# MiniHeating2.net
KiCad netlist of a schematic drawn in Altium Designer
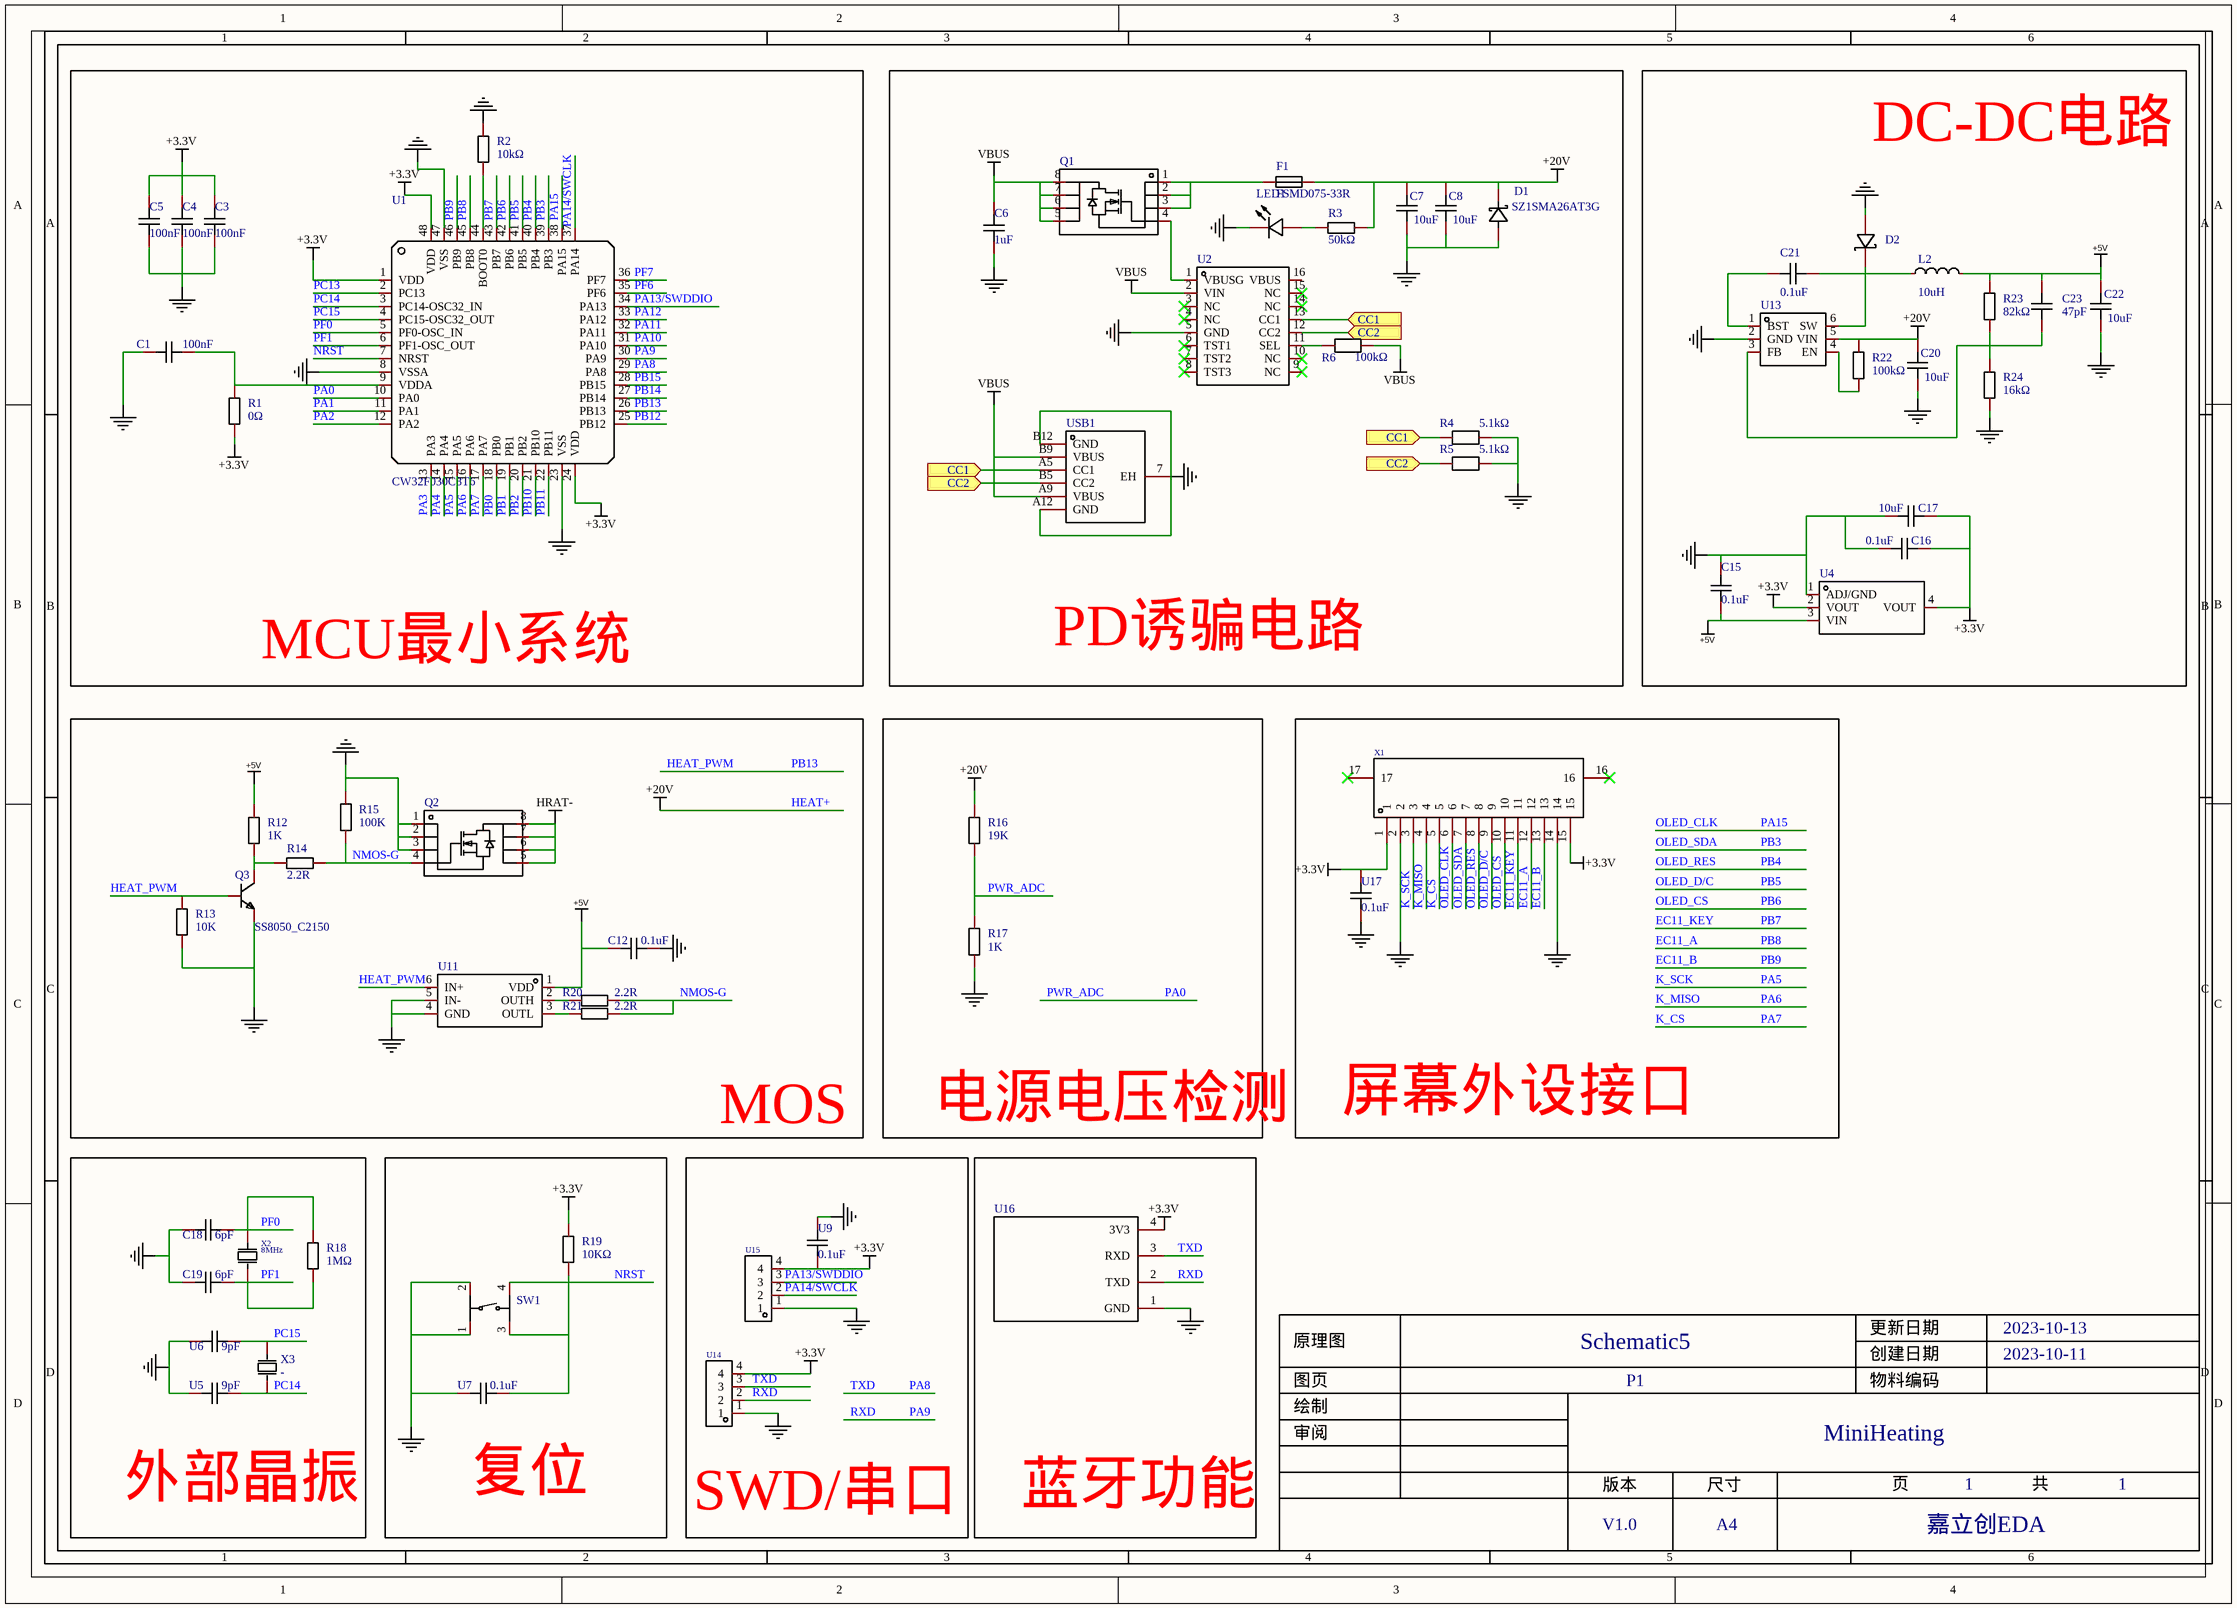
[diagram p0: MiniHeating2.schdoc]

(export (version "E")
  (design (tool "Eeschema 10.0.6"))
  (components
    (comp (ref "C1")
      (value "100nF")
      (description "容值:100nF;精度:±10%;额定电压:50V;材质(温度系数):X7R;")
      (fields
        (field (name "MANUFACTURER") "YAGEO(国巨)")
        (field (name "MANUFACTURER PART") "CC0603KRX7R9BB104")
      )
      (libsource (lib "altium-import") (part "root_0_CC0603KRX7R9BB104_"))
    )
    (comp (ref "C3")
      (value "100nF")
      (description "容值:100nF;精度:±10%;额定电压:50V;材质(温度系数):X7R;")
      (fields
        (field (name "MANUFACTURER") "YAGEO(国巨)")
        (field (name "MANUFACTURER PART") "CC0603KRX7R9BB104")
      )
      (libsource (lib "altium-import") (part "root_1_CC0603KRX7R9BB104_"))
    )
    (comp (ref "C4")
      (value "100nF")
      (description "容值:100nF;精度:±10%;额定电压:50V;材质(温度系数):X7R;")
      (fields
        (field (name "MANUFACTURER") "YAGEO(国巨)")
        (field (name "MANUFACTURER PART") "CC0603KRX7R9BB104")
      )
      (libsource (lib "altium-import") (part "root_1_CC0603KRX7R9BB104_"))
    )
    (comp (ref "C5")
      (value "100nF")
      (description "容值:100nF;精度:±10%;额定电压:50V;材质(温度系数):X7R;")
      (fields
        (field (name "MANUFACTURER") "YAGEO(国巨)")
        (field (name "MANUFACTURER PART") "CC0603KRX7R9BB104")
      )
      (libsource (lib "altium-import") (part "root_1_CC0603KRX7R9BB104_"))
    )
    (comp (ref "C6")
      (value "1uF")
      (description "容值:10uF;精度:±20%;额定电压:16V;材质(温度系数):-;")
      (fields (field (name "MANUFACTURER") "SAMSUNG(三星)") (field (name "MANUFACTURER PART") "10uF"))
      (libsource (lib "altium-import") (part "root_0_10uF_C15415_"))
    )
    (comp (ref "C7")
      (value "10uF")
      (description "容值:10uF;精度:±10%;额定电压:-;材质(温度系数):-;")
      (fields
        (field (name "NAME") "10uF")
        (field (name "MANUFACTURER") "muRata(村田)")
        (field (name "MANUFACTURER PART") "GRT21BC71E106KE13L")
      )
      (libsource (lib "altium-import") (part "root_1_GRT21BC71E106KE13L_"))
    )
    (comp (ref "C8")
      (value "10uF")
      (description "容值:10uF;精度:±10%;额定电压:-;材质(温度系数):-;")
      (fields
        (field (name "NAME") "10uF")
        (field (name "MANUFACTURER") "muRata(村田)")
        (field (name "MANUFACTURER PART") "GRT21BC71E106KE13L")
      )
      (libsource (lib "altium-import") (part "root_1_GRT21BC71E106KE13L_"))
    )
    (comp (ref "C12")
      (value "0.1uF")
      (description "容值:9pF;额定电压:50V;材质(温度系数):C0G;")
      (fields (field (name "MANUFACTURER") "TDK") (field (name "MANUFACTURER PART") "C1608C0G1H090D080AA"))
      (libsource (lib "altium-import") (part "root_0_C1608C0G1H090D080AA_"))
    )
    (comp (ref "C15")
      (value "0.1uF")
      (description "容值:0.1uF;精度:±10%;额定电压:50V;温度系数:-;")
      (fields
        (field (name "MANUFACTURER") "Knowles(楼氏)")
        (field (name "MANUFACTURER PART") "0603BB104K500NGT")
      )
      (libsource (lib "altium-import") (part "root_1_0603BB104K500NGT_"))
    )
    (comp (ref "C16")
      (value "0.1uF")
      (description "容值:0.1uF;精度:±10%;额定电压:50V;温度系数:-;")
      (fields
        (field (name "MANUFACTURER") "Knowles(楼氏)")
        (field (name "MANUFACTURER PART") "0603BB104K500NGT")
      )
      (libsource (lib "altium-import") (part "root_2_0603BB104K500NGT_"))
    )
    (comp (ref "C17")
      (value "10uF")
      (description "容值:10uF;精度:±10%;额定电压:-;材质(温度系数):-;")
      (fields
        (field (name "NAME") "10uF")
        (field (name "MANUFACTURER") "muRata(村田)")
        (field (name "MANUFACTURER PART") "GRT21BC71E106KE13L")
      )
      (libsource (lib "altium-import") (part "root_2_GRT21BC71E106KE13L_"))
    )
    (comp (ref "C18")
      (value "6pF")
      (description "容值:6pF;额定电压:50V;材质(温度系数):C0G;")
      (fields (field (name "MANUFACTURER") "TDK") (field (name "MANUFACTURER PART") "CGA3E2C0G1H060DT0Y0N"))
      (libsource (lib "altium-import") (part "root_0_CGA3E2C0G1H060DT0Y0N_"))
    )
    (comp (ref "C19")
      (value "6pF")
      (description "容值:6pF;额定电压:50V;材质(温度系数):C0G;")
      (fields (field (name "MANUFACTURER") "TDK") (field (name "MANUFACTURER PART") "CGA3E2C0G1H060DT0Y0N"))
      (libsource (lib "altium-import") (part "root_0_CGA3E2C0G1H060DT0Y0N_"))
    )
    (comp (ref "C20")
      (value "10uF")
      (description "容值:10uF;精度:±10%;额定电压:-;材质(温度系数):-;")
      (fields
        (field (name "NAME") "10uF")
        (field (name "MANUFACTURER") "muRata(村田)")
        (field (name "MANUFACTURER PART") "GRT21BC71E106KE13L")
      )
      (libsource (lib "altium-import") (part "root_1_GRT21BC71E106KE13L_"))
    )
    (comp (ref "C21")
      (value "0.1uF")
      (description "容值:0.1uF;精度:±10%;额定电压:50V;温度系数:-;")
      (fields
        (field (name "MANUFACTURER") "Knowles(楼氏)")
        (field (name "MANUFACTURER PART") "0603BB104K500NGT")
      )
      (libsource (lib "altium-import") (part "root_0_0603BB104K500NGT_"))
    )
    (comp (ref "C22")
      (value "10uF")
      (description "容值:10uF;精度:±10%;额定电压:-;材质(温度系数):-;")
      (fields
        (field (name "NAME") "10uF")
        (field (name "MANUFACTURER") "muRata(村田)")
        (field (name "MANUFACTURER PART") "GRT21BC71E106KE13L")
      )
      (libsource (lib "altium-import") (part "root_1_GRT21BC71E106KE13L_"))
    )
    (comp (ref "C23")
      (value "47pF")
      (description "容值:0.1uF;精度:±10%;额定电压:50V;温度系数:-;")
      (fields
        (field (name "MANUFACTURER") "Knowles(楼氏)")
        (field (name "MANUFACTURER PART") "0603BB104K500NGT")
      )
      (libsource (lib "altium-import") (part "root_1_0603BB104K500NGT_"))
    )
    (comp (ref "D1")
      (value "SZ1SMA26AT3G")
      (fields (field (name "NAME") "SZ1SMA26AT3G") (field (name "MANUFACTURER") "Littelfuse(美国力特)"))
      (libsource (lib "altium-import") (part "root_3_SZ1SMA26AT3G_"))
    )
    (comp (ref "D2")
      (value "SS34_C8678")
      (description "二极管配置:独立式;直流反向耐压(Vr):40V;平均整流电流(Io):3A;正向压降(Vf):550mV@3A;")
      (fields (field (name "MANUFACTURER") "MDD") (field (name "MANUFACTURER PART") "SS34"))
      (libsource (lib "altium-import") (part "root_1_SS34_C8678_"))
    )
    (comp (ref "F1")
      (value "FSMD075-33R")
      (description "最大电压:33V;最大电流:40A;保持电流:750mA;跳闸电流:1.5A;")
      (fields (field (name "NAME") "FSMD075-33R") (field (name "MANUFACTURER") "FUZETEC(台湾富致)"))
      (libsource (lib "altium-import") (part "root_0_FSMD075-33R_"))
    )
    (comp (ref "L2")
      (value "10uH")
      (description "类型:-;电感值:10uH;精度:±20%;额定电流:2.45A;饱和电流(Isat):3.5A;")
      (fields (field (name "MANUFACTURER") "Sunlord(顺络)") (field (name "MANUFACTURER PART") "SWPA6045S100MT"))
      (libsource (lib "altium-import") (part "root_0_SWPA6045S100MT_"))
    )
    (comp (ref "LED1")
      (value "KT-0603R")
      (description "发光颜色:红灯;二极管配置:-;透镜颜色:-;主波长:-;色温:-;功率:-;发光角度:-;安装方式:-;工作温度:-40℃~+85℃;")
      (fields (field (name "MANUFACTURER") "KENTO"))
      (libsource (lib "altium-import") (part "root_0_KT-0603R_"))
    )
    (comp (ref "Q1")
      (value "BSC123N08NS3 G")
      (libsource (lib "altium-import") (part "root_0_mirrored_BSC123N08NS3 G_"))
    )
    (comp (ref "Q2")
      (value "BSC123N08NS3 G")
      (libsource (lib "altium-import") (part "root_0_BSC123N08NS3 G_"))
    )
    (comp (ref "Q3")
      (value "SS8050_C2150")
      (description "晶体管类型:NPN;集射极击穿电压(Vceo):25V;集电极电流(Ic):1.5A;功率(Pd):300mW;直流电流增益(hFE@Ic,Vce):200@100mA,1V;")
      (fields
        (field (name "DEVICE") "SS8050_C2150")
        (field (name "MANUFACTURER") "CJ(江苏长电/长晶)")
        (field (name "MANUFACTURER PART") "SS8050")
      )
      (libsource (lib "altium-import") (part "root_0_SS8050_C2150_"))
    )
    (comp (ref "R1")
      (value "0Ω")
      (description "电阻类型:厚膜电阻;阻值:470kΩ;精度:±1%;功率:100mW;")
      (fields
        (field (name "MANUFACTURER") "UNI-ROYAL(厚声)")
        (field (name "MANUFACTURER PART") "0603WAF4703T5E")
      )
      (libsource (lib "altium-import") (part "root_1_0603WAF4703T5E_"))
    )
    (comp (ref "R2")
      (value "10kΩ")
      (description "电阻类型:厚膜电阻;阻值:24kΩ;精度:±1%;功率:100mW;")
      (fields
        (field (name "MANUFACTURER") "UNI-ROYAL(厚声)")
        (field (name "MANUFACTURER PART") "0603WAF2402T5E")
      )
      (libsource (lib "altium-import") (part "root_1_0603WAF2402T5E_"))
    )
    (comp (ref "R3")
      (value "50kΩ")
      (description "电阻类型:薄膜电阻;阻值:10kΩ;精度:±0.1%;功率:63mW;")
      (fields
        (field (name "MANUFACTURER") "SEI(Stackpole Electronics Inc.)")
        (field (name "MANUFACTURER PART") "RNCS0603BKE10K0")
      )
      (libsource (lib "altium-import") (part "root_2_RNCS0603BKE10K0_"))
    )
    (comp (ref "R4")
      (value "5.1kΩ")
      (description "电阻类型:厚膜电阻;阻值:10kΩ;精度:±0.5%;功率:100mW;")
      (fields (field (name "MANUFACTURER") "YAGEO(国巨)") (field (name "MANUFACTURER PART") "AC0603DR-0710KL"))
      (libsource (lib "altium-import") (part "root_0_AC0603DR-0710KL_"))
    )
    (comp (ref "R5")
      (value "5.1kΩ")
      (description "电阻类型:厚膜电阻;阻值:10kΩ;精度:±0.5%;功率:100mW;")
      (fields (field (name "MANUFACTURER") "YAGEO(国巨)") (field (name "MANUFACTURER PART") "AC0603DR-0710KL"))
      (libsource (lib "altium-import") (part "root_0_AC0603DR-0710KL_"))
    )
    (comp (ref "R6")
      (value "100kΩ")
      (description "阻值:100kΩ;功率:125mW;")
      (fields
        (field (name "NAME") "100kΩ")
        (field (name "MANUFACTURER") "Milliohm(毫欧)")
        (field (name "MANUFACTURER PART") "HoLTT0805-1/8W-100K-5%")
      )
      (libsource (lib "altium-import") (part "root_0_HoLTT0805-1/8W-100K-5%_"))
    )
    (comp (ref "R12")
      (value "1K")
      (description "电阻类型:厚膜电阻;阻值:470kΩ;精度:±1%;功率:100mW;")
      (fields
        (field (name "MANUFACTURER") "UNI-ROYAL(厚声)")
        (field (name "MANUFACTURER PART") "0603WAF4703T5E")
      )
      (libsource (lib "altium-import") (part "root_1_0603WAF4703T5E_"))
    )
    (comp (ref "R13")
      (value "10K")
      (description "电阻类型:厚膜电阻;阻值:470kΩ;精度:±1%;功率:100mW;")
      (fields
        (field (name "MANUFACTURER") "UNI-ROYAL(厚声)")
        (field (name "MANUFACTURER PART") "0603WAF4703T5E")
      )
      (libsource (lib "altium-import") (part "root_1_0603WAF4703T5E_"))
    )
    (comp (ref "R14")
      (value "2.2R")
      (description "电阻类型:厚膜电阻;阻值:470kΩ;精度:±1%;功率:100mW;")
      (fields
        (field (name "MANUFACTURER") "UNI-ROYAL(厚声)")
        (field (name "MANUFACTURER PART") "0603WAF4703T5E")
      )
      (libsource (lib "altium-import") (part "root_2_0603WAF4703T5E_"))
    )
    (comp (ref "R15")
      (value "100K")
      (description "电阻类型:厚膜电阻;阻值:470kΩ;精度:±1%;功率:100mW;")
      (fields
        (field (name "MANUFACTURER") "UNI-ROYAL(厚声)")
        (field (name "MANUFACTURER PART") "0603WAF4703T5E")
      )
      (libsource (lib "altium-import") (part "root_1_0603WAF4703T5E_"))
    )
    (comp (ref "R16")
      (value "19K")
      (description "电阻类型:厚膜电阻;阻值:470kΩ;精度:±1%;功率:100mW;")
      (fields
        (field (name "MANUFACTURER") "UNI-ROYAL(厚声)")
        (field (name "MANUFACTURER PART") "0603WAF4703T5E")
      )
      (libsource (lib "altium-import") (part "root_1_0603WAF4703T5E_"))
    )
    (comp (ref "R17")
      (value "1K")
      (description "电阻类型:厚膜电阻;阻值:470kΩ;精度:±1%;功率:100mW;")
      (fields
        (field (name "MANUFACTURER") "UNI-ROYAL(厚声)")
        (field (name "MANUFACTURER PART") "0603WAF4703T5E")
      )
      (libsource (lib "altium-import") (part "root_1_0603WAF4703T5E_"))
    )
    (comp (ref "R18")
      (value "1MΩ")
      (description "电阻类型:厚膜电阻;阻值:1MΩ;精度:±1%;功率:100mW;")
      (fields
        (field (name "MANUFACTURER") "UNI-ROYAL(厚声)")
        (field (name "MANUFACTURER PART") "0603WAF1004T5E")
      )
      (libsource (lib "altium-import") (part "root_1_0603WAF1004T5E_"))
    )
    (comp (ref "R19")
      (value "10KΩ")
      (description "电阻类型:厚膜电阻;阻值:1MΩ;精度:±1%;功率:100mW;")
      (fields
        (field (name "MANUFACTURER") "UNI-ROYAL(厚声)")
        (field (name "MANUFACTURER PART") "0603WAF1004T5E")
      )
      (libsource (lib "altium-import") (part "root_1_0603WAF1004T5E_"))
    )
    (comp (ref "R20")
      (value "2.2R")
      (description "电阻类型:厚膜电阻;阻值:470kΩ;精度:±1%;功率:100mW;")
      (fields
        (field (name "MANUFACTURER") "UNI-ROYAL(厚声)")
        (field (name "MANUFACTURER PART") "0603WAF4703T5E")
      )
      (libsource (lib "altium-import") (part "root_2_0603WAF4703T5E_"))
    )
    (comp (ref "R21")
      (value "2.2R")
      (description "电阻类型:厚膜电阻;阻值:470kΩ;精度:±1%;功率:100mW;")
      (fields
        (field (name "MANUFACTURER") "UNI-ROYAL(厚声)")
        (field (name "MANUFACTURER PART") "0603WAF4703T5E")
      )
      (libsource (lib "altium-import") (part "root_2_0603WAF4703T5E_"))
    )
    (comp (ref "R22")
      (value "100kΩ")
      (description "阻值:50kΩ;精度:±0.1%;功率:62.5mW;")
      (fields (field (name "MANUFACTURER") "Viking(光颉)") (field (name "MANUFACTURER PART") "AR03BTC5002A"))
      (libsource (lib "altium-import") (part "root_1_AR03BTC5002A_"))
    )
    (comp (ref "R23")
      (value "82kΩ")
      (description "阻值:50kΩ;精度:±0.1%;功率:62.5mW;")
      (fields (field (name "MANUFACTURER") "Viking(光颉)") (field (name "MANUFACTURER PART") "AR03BTC5002A"))
      (libsource (lib "altium-import") (part "root_1_AR03BTC5002A_"))
    )
    (comp (ref "R24")
      (value "16kΩ")
      (description "阻值:50kΩ;精度:±0.1%;功率:62.5mW;")
      (fields (field (name "MANUFACTURER") "Viking(光颉)") (field (name "MANUFACTURER PART") "AR03BTC5002A"))
      (libsource (lib "altium-import") (part "root_1_AR03BTC5002A_"))
    )
    (comp (ref "SW1")
      (value "TS-1186D-C-A")
      (description "触点电流:50mA;额定电压(DC):12V;绝缘电阻:-;电路结构:单刀单掷;安装方式:卧贴;带灯:无;作用力:260gf;机械寿命:10万次;带支架:否;")
      (fields (field (name "MANUFACTURER") "XKB Connectivity(中国星坤)"))
      (libsource (lib "altium-import") (part "root_1_TS-1186D-C-A_"))
    )
    (comp (ref "U1")
      (value "CW32F030C8T6")
      (fields (field (name "NAME") "CW32F030C8T6") (field (name "MANUFACTURER") "CW(芯源)"))
      (libsource (lib "altium-import") (part "root_0_CW32F030C8T6_C3019113_"))
    )
    (comp (ref "U2")
      (value "IP2721")
      (fields (field (name "MANUFACTURER") "INJOINIC(英集芯)"))
      (libsource (lib "altium-import") (part "root_0_IP2721_"))
    )
    (comp (ref "U4")
      (value "LM1117GS-3.3")
      (description "输出类型:-;")
      (fields (field (name "MANUFACTURER") "HTC"))
      (libsource (lib "altium-import") (part "root_0_LM1117GS-3.3_"))
    )
    (comp (ref "U5")
      (value "9pF")
      (description "容值:9pF;额定电压:50V;材质(温度系数):C0G;")
      (fields (field (name "MANUFACTURER") "TDK") (field (name "MANUFACTURER PART") "C1608C0G1H090D080AA"))
      (libsource (lib "altium-import") (part "root_0_C1608C0G1H090D080AA_"))
    )
    (comp (ref "U6")
      (value "9pF")
      (description "容值:9pF;额定电压:50V;材质(温度系数):C0G;")
      (fields (field (name "MANUFACTURER") "TDK") (field (name "MANUFACTURER PART") "C1608C0G1H090D080AA"))
      (libsource (lib "altium-import") (part "root_0_C1608C0G1H090D080AA_"))
    )
    (comp (ref "U7")
      (value "0.1uF")
      (description "容值:9pF;额定电压:50V;材质(温度系数):C0G;")
      (fields (field (name "MANUFACTURER") "TDK") (field (name "MANUFACTURER PART") "C1608C0G1H090D080AA"))
      (libsource (lib "altium-import") (part "root_0_C1608C0G1H090D080AA_"))
    )
    (comp (ref "U9")
      (value "0.1uF")
      (description "容值:9pF;额定电压:50V;材质(温度系数):C0G;")
      (fields (field (name "MANUFACTURER") "TDK") (field (name "MANUFACTURER PART") "C1608C0G1H090D080AA"))
      (libsource (lib "altium-import") (part "root_1_C1608C0G1H090D080AA_"))
    )
    (comp (ref "U11")
      (value "UCC27511DBVR")
      (description "驱动配置:低边;负载类型:MOSFET；IGBT;电源电压:4.5V~18V;峰值灌电流:8A;峰值拉电流:4A;")
      (fields (field (name "MANUFACTURER") "TI(德州仪器)"))
      (libsource (lib "altium-import") (part "root_0_mirrored_UCC27511DBVR_"))
    )
    (comp (ref "U13")
      (value "LGS5145")
      (description "功能类型:降压型;输出类型:可调;输入电压:4.5V~55V;输出电压:800mV~40V;输出电流(最大值):1A;")
      (fields (field (name "MANUFACTURER") "Legend-Si(棱晶半导体)"))
      (libsource (lib "altium-import") (part "root_0_LGS5145_"))
    )
    (comp (ref "U14")
      (value "ZX-PZ2.54-1-4PZZ")
      (fields (field (name "MANUFACTURER") "Megastar(兆星)"))
      (libsource (lib "altium-import") (part "root_2_ZX-PZ2.54-1-4PZZ_"))
    )
    (comp (ref "U15")
      (value "ZX-PZ2.54-1-4PZZ")
      (fields (field (name "MANUFACTURER") "Megastar(兆星)"))
      (libsource (lib "altium-import") (part "root_2_ZX-PZ2.54-1-4PZZ_"))
    )
    (comp (ref "U16")
      (value "ECB01H2")
      (description "ECB01H2模块")
      (libsource (lib "altium-import") (part "root_1_ECB01H2_"))
    )
    (comp (ref "U17")
      (value "0.1uF")
      (description "容值:9pF;额定电压:50V;材质(温度系数):C0G;")
      (fields (field (name "MANUFACTURER") "TDK") (field (name "MANUFACTURER PART") "C1608C0G1H090D080AA"))
      (libsource (lib "altium-import") (part "root_1_C1608C0G1H090D080AA_"))
    )
    (comp (ref "USB1")
      (value "TYPE-C-6P-DIP2X2")
      (libsource (lib "altium-import") (part "root_0_TYPE-C-6P-DIP2X2_"))
    )
    (comp (ref "X1")
      (value "AFC01-S15FCA-00")
      (description "间距:0.5mm;触点数量:15;锁定特性:翻盖式;安装类型:卧贴;触点类型:下接;工作温度范围:-;")
      (fields (field (name "MANUFACTURER") "JS(钜硕电子)"))
      (libsource (lib "altium-import") (part "root_1_AFC01-S15FCA-00_"))
    )
    (comp (ref "X2")
      (value "8MHz")
      (description "频率:8MHz;频率公差:±30ppm;负载电容:20pF;")
      (fields (field (name "MANUFACTURER") "TAE(雅晶鑫)") (field (name "MANUFACTURER PART") "TAXD8M2GLFBET2T"))
      (libsource (lib "altium-import") (part "root_1_TAXD8M2GLFBET2T_"))
    )
    (comp (ref "X3")
      (value "-")
      (description "频率:-;负载电容:-;")
      (fields (field (name "MANUFACTURER") "TKD(泰晶)") (field (name "MANUFACTURER PART") "SF32WK32768D31T002"))
      (libsource (lib "altium-import") (part "root_1_SF32WK32768D31T002_"))
    )
  )
  (nets
    (net (code "1") (name "+3.3V") (class "Default")
      (node (ref "C16") (pin "1") (pinfunction "1_1") (pintype "passive"))
      (node (ref "C17") (pin "1") (pinfunction "1_1") (pintype "passive"))
      (node (ref "C3") (pin "2") (pinfunction "2_2") (pintype "passive"))
      (node (ref "C4") (pin "2") (pinfunction "2_2") (pintype "passive"))
      (node (ref "C5") (pin "2") (pinfunction "2_2") (pintype "passive"))
      (node (ref "R1") (pin "1") (pinfunction "1_1") (pintype "passive"))
      (node (ref "R19") (pin "2") (pinfunction "2_2") (pintype "passive"))
      (node (ref "U1") (pin "1") (pinfunction "VDD_1") (pintype "passive"))
      (node (ref "U1") (pin "24") (pinfunction "VDD_24") (pintype "passive"))
      (node (ref "U1") (pin "48") (pinfunction "VDD_48") (pintype "passive"))
      (node (ref "U14") (pin "4") (pinfunction "4_4") (pintype "passive"))
      (node (ref "U15") (pin "4") (pinfunction "4_4") (pintype "passive"))
      (node (ref "U16") (pin "4") (pinfunction "3V3_4") (pintype "passive"))
      (node (ref "U17") (pin "2") (pinfunction "2_2") (pintype "passive"))
      (node (ref "U4") (pin "2") (pinfunction "VOUT_2") (pintype "passive"))
      (node (ref "U4") (pin "4") (pinfunction "VOUT_4") (pintype "passive"))
      (node (ref "U9") (pin "1") (pinfunction "1_1") (pintype "passive"))
      (node (ref "X1") (pin "1") (pinfunction "1_1") (pintype "passive"))
      (node (ref "X1") (pin "15") (pinfunction "15_15") (pintype "passive"))
    )
    (net (code "2") (name "+5V") (class "Default")
      (node (ref "C12") (pin "1") (pinfunction "1_1") (pintype "passive"))
      (node (ref "C15") (pin "1") (pinfunction "1_1") (pintype "passive"))
      (node (ref "C22") (pin "2") (pinfunction "2_2") (pintype "passive"))
      (node (ref "C23") (pin "2") (pinfunction "2_2") (pintype "passive"))
      (node (ref "L2") (pin "2") (pinfunction "2_2") (pintype "passive"))
      (node (ref "R12") (pin "2") (pinfunction "2_2") (pintype "passive"))
      (node (ref "R23") (pin "2") (pinfunction "2_2") (pintype "passive"))
      (node (ref "U11") (pin "1") (pinfunction "VDD_1") (pintype "passive"))
      (node (ref "U4") (pin "3") (pinfunction "VIN_3") (pintype "passive"))
    )
    (net (code "3") (name "+20V") (class "Default")
      (node (ref "C20") (pin "2") (pinfunction "2_2") (pintype "passive"))
      (node (ref "C7") (pin "2") (pinfunction "2_2") (pintype "passive"))
      (node (ref "C8") (pin "2") (pinfunction "2_2") (pintype "passive"))
      (node (ref "D1") (pin "2") (pinfunction "K_2") (pintype "passive"))
      (node (ref "F1") (pin "2") (pinfunction "2_2") (pintype "passive"))
      (node (ref "R16") (pin "2") (pinfunction "2_2") (pintype "passive"))
      (node (ref "R22") (pin "2") (pinfunction "2_2") (pintype "passive"))
      (node (ref "R3") (pin "1") (pinfunction "1_1") (pintype "passive"))
      (node (ref "U13") (pin "5") (pinfunction "VIN_5") (pintype "passive"))
    )
    (net (code "4") (name "/CC1") (class "Default")
      (node (ref "R4") (pin "1") (pinfunction "1_1") (pintype "passive"))
      (node (ref "U2") (pin "13") (pinfunction "CC1_13") (pintype "passive"))
      (node (ref "USB1") (pin "A5") (pinfunction "CC1_A5") (pintype "passive"))
    )
    (net (code "5") (name "/CC2") (class "Default")
      (node (ref "R5") (pin "1") (pinfunction "1_1") (pintype "passive"))
      (node (ref "U2") (pin "12") (pinfunction "CC2_12") (pintype "passive"))
      (node (ref "USB1") (pin "B5") (pinfunction "CC2_B5") (pintype "passive"))
    )
    (net (code "6") (name "/EC11_A") (class "Default")
      (node (ref "U1") (pin "45") (pinfunction "PB8_45") (pintype "passive"))
      (node (ref "X1") (pin "12") (pinfunction "12_12") (pintype "passive"))
    )
    (net (code "7") (name "/EC11_B") (class "Default")
      (node (ref "U1") (pin "46") (pinfunction "PB9_46") (pintype "passive"))
      (node (ref "X1") (pin "13") (pinfunction "13_13") (pintype "passive"))
    )
    (net (code "8") (name "/EC11_KEY") (class "Default")
      (node (ref "U1") (pin "43") (pinfunction "PB7_43") (pintype "passive"))
      (node (ref "X1") (pin "11") (pinfunction "11_11") (pintype "passive"))
    )
    (net (code "9") (name "/HEAT_PWM") (class "Default")
      (node (ref "Q3") (pin "1") (pinfunction "B_1") (pintype "passive"))
      (node (ref "R13") (pin "2") (pinfunction "2_2") (pintype "passive"))
      (node (ref "U1") (pin "26") (pinfunction "PB13_26") (pintype "passive"))
      (node (ref "U11") (pin "6") (pinfunction "IN+_6") (pintype "passive"))
    )
    (net (code "10") (name "/K_CS") (class "Default")
      (node (ref "U1") (pin "17") (pinfunction "PA7_17") (pintype "passive"))
      (node (ref "X1") (pin "5") (pinfunction "5_5") (pintype "passive"))
    )
    (net (code "11") (name "/K_MISO") (class "Default")
      (node (ref "U1") (pin "16") (pinfunction "PA6_16") (pintype "passive"))
      (node (ref "X1") (pin "4") (pinfunction "4_4") (pintype "passive"))
    )
    (net (code "12") (name "/K_SCK") (class "Default")
      (node (ref "U1") (pin "15") (pinfunction "PA5_15") (pintype "passive"))
      (node (ref "X1") (pin "3") (pinfunction "3_3") (pintype "passive"))
    )
    (net (code "13") (name "/NMOS-G") (class "Default")
      (node (ref "Q2") (pin "4") (pinfunction "G_4") (pintype "passive"))
      (node (ref "R14") (pin "1") (pinfunction "1_1") (pintype "passive"))
      (node (ref "R15") (pin "1") (pinfunction "1_1") (pintype "passive"))
      (node (ref "R20") (pin "1") (pinfunction "1_1") (pintype "passive"))
      (node (ref "R21") (pin "1") (pinfunction "1_1") (pintype "passive"))
    )
    (net (code "14") (name "/NRST") (class "Default")
      (node (ref "R19") (pin "1") (pinfunction "1_1") (pintype "passive"))
      (node (ref "SW1") (pin "3") (pinfunction "3_3") (pintype "passive"))
      (node (ref "SW1") (pin "4") (pinfunction "4_4") (pintype "passive"))
      (node (ref "U1") (pin "7") (pinfunction "NRST_7") (pintype "passive"))
      (node (ref "U7") (pin "2") (pinfunction "2_2") (pintype "passive"))
    )
    (net (code "15") (name "/OLED_CLK") (class "Default")
      (node (ref "U1") (pin "38") (pinfunction "PA15_38") (pintype "passive"))
      (node (ref "X1") (pin "6") (pinfunction "6_6") (pintype "passive"))
    )
    (net (code "16") (name "/OLED_CS") (class "Default")
      (node (ref "U1") (pin "42") (pinfunction "PB6_42") (pintype "passive"))
      (node (ref "X1") (pin "10") (pinfunction "10_10") (pintype "passive"))
    )
    (net (code "17") (name "/OLED_D{slash}C") (class "Default")
      (node (ref "U1") (pin "41") (pinfunction "PB5_41") (pintype "passive"))
      (node (ref "X1") (pin "9") (pinfunction "9_9") (pintype "passive"))
    )
    (net (code "18") (name "/OLED_RES") (class "Default")
      (node (ref "U1") (pin "40") (pinfunction "PB4_40") (pintype "passive"))
      (node (ref "X1") (pin "8") (pinfunction "8_8") (pintype "passive"))
    )
    (net (code "19") (name "/OLED_SDA") (class "Default")
      (node (ref "U1") (pin "39") (pinfunction "PB3_39") (pintype "passive"))
      (node (ref "X1") (pin "7") (pinfunction "7_7") (pintype "passive"))
    )
    (net (code "20") (name "/PA0") (class "Default")
      (node (ref "R16") (pin "1") (pinfunction "1_1") (pintype "passive"))
      (node (ref "R17") (pin "2") (pinfunction "2_2") (pintype "passive"))
      (node (ref "U1") (pin "10") (pinfunction "PA0_10") (pintype "passive"))
    )
    (net (code "21") (name "/PA1") (class "Default")
      (node (ref "U1") (pin "11") (pinfunction "PA1_11") (pintype "passive"))
    )
    (net (code "22") (name "/PA2") (class "Default")
      (node (ref "U1") (pin "12") (pinfunction "PA2_12") (pintype "passive"))
    )
    (net (code "23") (name "/PA3") (class "Default")
      (node (ref "U1") (pin "13") (pinfunction "PA3_13") (pintype "passive"))
    )
    (net (code "24") (name "/PA4") (class "Default")
      (node (ref "U1") (pin "14") (pinfunction "PA4_14") (pintype "passive"))
    )
    (net (code "25") (name "/PA8") (class "Default")
      (node (ref "U1") (pin "29") (pinfunction "PA8_29") (pintype "passive"))
      (node (ref "U14") (pin "3") (pinfunction "3_3") (pintype "passive"))
      (node (ref "U16") (pin "3") (pinfunction "RXD_3") (pintype "passive"))
    )
    (net (code "26") (name "/PA9") (class "Default")
      (node (ref "U1") (pin "30") (pinfunction "PA9_30") (pintype "passive"))
      (node (ref "U14") (pin "2") (pinfunction "2_2") (pintype "passive"))
      (node (ref "U16") (pin "2") (pinfunction "TXD_2") (pintype "passive"))
    )
    (net (code "27") (name "/PA10") (class "Default")
      (node (ref "U1") (pin "31") (pinfunction "PA10_31") (pintype "passive"))
    )
    (net (code "28") (name "/PA11") (class "Default")
      (node (ref "U1") (pin "32") (pinfunction "PA11_32") (pintype "passive"))
    )
    (net (code "29") (name "/PA12") (class "Default")
      (node (ref "U1") (pin "33") (pinfunction "PA12_33") (pintype "passive"))
    )
    (net (code "30") (name "/PA13{slash}SWDDIO") (class "Default")
      (node (ref "U1") (pin "34") (pinfunction "PA13_34") (pintype "passive"))
      (node (ref "U15") (pin "3") (pinfunction "3_3") (pintype "passive"))
    )
    (net (code "31") (name "/PA14{slash}SWCLK") (class "Default")
      (node (ref "U1") (pin "37") (pinfunction "PA14_37") (pintype "passive"))
      (node (ref "U15") (pin "2") (pinfunction "2_2") (pintype "passive"))
    )
    (net (code "32") (name "/PB0") (class "Default")
      (node (ref "U1") (pin "18") (pinfunction "PB0_18") (pintype "passive"))
    )
    (net (code "33") (name "/PB1") (class "Default")
      (node (ref "U1") (pin "19") (pinfunction "PB1_19") (pintype "passive"))
    )
    (net (code "34") (name "/PB2") (class "Default")
      (node (ref "U1") (pin "20") (pinfunction "PB2_20") (pintype "passive"))
    )
    (net (code "35") (name "/PB10") (class "Default")
      (node (ref "U1") (pin "21") (pinfunction "PB10_21") (pintype "passive"))
    )
    (net (code "36") (name "/PB11") (class "Default")
      (node (ref "U1") (pin "22") (pinfunction "PB11_22") (pintype "passive"))
    )
    (net (code "37") (name "/PB12") (class "Default")
      (node (ref "U1") (pin "25") (pinfunction "PB12_25") (pintype "passive"))
    )
    (net (code "38") (name "/PB14") (class "Default")
      (node (ref "U1") (pin "27") (pinfunction "PB14_27") (pintype "passive"))
    )
    (net (code "39") (name "/PB15") (class "Default")
      (node (ref "U1") (pin "28") (pinfunction "PB15_28") (pintype "passive"))
    )
    (net (code "40") (name "/PC13") (class "Default")
      (node (ref "U1") (pin "2") (pinfunction "PC13_2") (pintype "passive"))
    )
    (net (code "41") (name "/PC14") (class "Default")
      (node (ref "U1") (pin "3") (pinfunction "PC14-OSC32_IN_3") (pintype "passive"))
      (node (ref "U5") (pin "2") (pinfunction "2_2") (pintype "passive"))
      (node (ref "X3") (pin "1") (pinfunction "OSC1_1") (pintype "passive"))
    )
    (net (code "42") (name "/PC15") (class "Default")
      (node (ref "U1") (pin "4") (pinfunction "PC15-OSC32_OUT_4") (pintype "passive"))
      (node (ref "U6") (pin "2") (pinfunction "2_2") (pintype "passive"))
      (node (ref "X3") (pin "2") (pinfunction "OSC2_2") (pintype "passive"))
    )
    (net (code "43") (name "/PF0") (class "Default")
      (node (ref "C18") (pin "2") (pinfunction "2_2") (pintype "passive"))
      (node (ref "R18") (pin "2") (pinfunction "2_2") (pintype "passive"))
      (node (ref "U1") (pin "5") (pinfunction "PF0-OSC_IN_5") (pintype "passive"))
      (node (ref "X2") (pin "2") (pinfunction "OSC2_2") (pintype "passive"))
    )
    (net (code "44") (name "/PF1") (class "Default")
      (node (ref "C19") (pin "2") (pinfunction "2_2") (pintype "passive"))
      (node (ref "R18") (pin "1") (pinfunction "1_1") (pintype "passive"))
      (node (ref "U1") (pin "6") (pinfunction "PF1-OSC_OUT_6") (pintype "passive"))
      (node (ref "X2") (pin "1") (pinfunction "OSC1_1") (pintype "passive"))
    )
    (net (code "45") (name "/PF6") (class "Default")
      (node (ref "U1") (pin "35") (pinfunction "PF6_35") (pintype "passive"))
    )
    (net (code "46") (name "/PF7") (class "Default")
      (node (ref "U1") (pin "36") (pinfunction "PF7_36") (pintype "passive"))
    )
    (net (code "47") (name "<NO NET>") (class "Default")
      (node (ref "C1") (pin "1") (pinfunction "1_1") (pintype "passive"))
      (node (ref "C12") (pin "2") (pinfunction "2_2") (pintype "passive"))
      (node (ref "C15") (pin "2") (pinfunction "2_2") (pintype "passive"))
      (node (ref "C16") (pin "2") (pinfunction "2_2") (pintype "passive"))
      (node (ref "C17") (pin "2") (pinfunction "2_2") (pintype "passive"))
      (node (ref "C18") (pin "1") (pinfunction "1_1") (pintype "passive"))
      (node (ref "C19") (pin "1") (pinfunction "1_1") (pintype "passive"))
      (node (ref "C20") (pin "1") (pinfunction "1_1") (pintype "passive"))
      (node (ref "C22") (pin "1") (pinfunction "1_1") (pintype "passive"))
      (node (ref "C3") (pin "1") (pinfunction "1_1") (pintype "passive"))
      (node (ref "C4") (pin "1") (pinfunction "1_1") (pintype "passive"))
      (node (ref "C5") (pin "1") (pinfunction "1_1") (pintype "passive"))
      (node (ref "C6") (pin "1") (pinfunction "1_1") (pintype "passive"))
      (node (ref "C7") (pin "1") (pinfunction "1_1") (pintype "passive"))
      (node (ref "C8") (pin "1") (pinfunction "1_1") (pintype "passive"))
      (node (ref "D1") (pin "1") (pinfunction "A_1") (pintype "passive"))
      (node (ref "D2") (pin "2") (pinfunction "A_2") (pintype "passive"))
      (node (ref "LED1") (pin "1") (pinfunction "K_1") (pintype "passive"))
      (node (ref "Q2") (pin "1") (pinfunction "S_1") (pintype "passive"))
      (node (ref "Q2") (pin "2") (pinfunction "S_2") (pintype "passive"))
      (node (ref "Q2") (pin "3") (pinfunction "S_3") (pintype "passive"))
      (node (ref "Q3") (pin "2") (pinfunction "E_2") (pintype "passive"))
      (node (ref "R13") (pin "1") (pinfunction "1_1") (pintype "passive"))
      (node (ref "R15") (pin "2") (pinfunction "2_2") (pintype "passive"))
      (node (ref "R17") (pin "1") (pinfunction "1_1") (pintype "passive"))
      (node (ref "R2") (pin "2") (pinfunction "2_2") (pintype "passive"))
      (node (ref "R24") (pin "1") (pinfunction "1_1") (pintype "passive"))
      (node (ref "R4") (pin "2") (pinfunction "2_2") (pintype "passive"))
      (node (ref "R5") (pin "2") (pinfunction "2_2") (pintype "passive"))
      (node (ref "SW1") (pin "1") (pinfunction "1_1") (pintype "passive"))
      (node (ref "SW1") (pin "2") (pinfunction "2_2") (pintype "passive"))
      (node (ref "U1") (pin "23") (pinfunction "VSS_23") (pintype "passive"))
      (node (ref "U1") (pin "47") (pinfunction "VSS_47") (pintype "passive"))
      (node (ref "U1") (pin "8") (pinfunction "VSSA_8") (pintype "passive"))
      (node (ref "U11") (pin "4") (pinfunction "GND_4") (pintype "passive"))
      (node (ref "U11") (pin "5") (pinfunction "IN-_5") (pintype "passive"))
      (node (ref "U13") (pin "2") (pinfunction "GND_2") (pintype "passive"))
      (node (ref "U14") (pin "1") (pinfunction "1_1") (pintype "passive"))
      (node (ref "U15") (pin "1") (pinfunction "1_1") (pintype "passive"))
      (node (ref "U16") (pin "1") (pinfunction "GND_1") (pintype "passive"))
      (node (ref "U17") (pin "1") (pinfunction "1_1") (pintype "passive"))
      (node (ref "U2") (pin "5") (pinfunction "GND_5") (pintype "passive"))
      (node (ref "U4") (pin "1") (pinfunction "ADJ/GND_1") (pintype "passive"))
      (node (ref "U5") (pin "1") (pinfunction "1_1") (pintype "passive"))
      (node (ref "U6") (pin "1") (pinfunction "1_1") (pintype "passive"))
      (node (ref "U7") (pin "1") (pinfunction "1_1") (pintype "passive"))
      (node (ref "U9") (pin "2") (pinfunction "2_2") (pintype "passive"))
      (node (ref "USB1") (pin "7") (pinfunction "EH_7") (pintype "passive"))
      (node (ref "USB1") (pin "A12") (pinfunction "GND_A12") (pintype "passive"))
      (node (ref "USB1") (pin "B12") (pinfunction "GND_B12") (pintype "passive"))
      (node (ref "X1") (pin "14") (pinfunction "14_14") (pintype "passive"))
      (node (ref "X1") (pin "2") (pinfunction "2_2") (pintype "passive"))
    )
    (net (code "48") (name "HRAT-") (class "Default")
      (node (ref "Q2") (pin "5") (pinfunction "D_5") (pintype "passive"))
      (node (ref "Q2") (pin "6") (pinfunction "D_6") (pintype "passive"))
      (node (ref "Q2") (pin "7") (pinfunction "D_7") (pintype "passive"))
      (node (ref "Q2") (pin "8") (pinfunction "D_8") (pintype "passive"))
    )
    (net (code "49") (name "Net-(D2-K)") (class "Default")
      (node (ref "C21") (pin "2") (pinfunction "2_2") (pintype "passive"))
      (node (ref "D2") (pin "1") (pinfunction "K_1") (pintype "passive"))
      (node (ref "L2") (pin "1") (pinfunction "1_1") (pintype "passive"))
      (node (ref "U13") (pin "6") (pinfunction "SW_6") (pintype "passive"))
    )
    (net (code "50") (name "Net-(F1-Pad1)") (class "Default")
      (node (ref "F1") (pin "1") (pinfunction "1_1") (pintype "passive"))
      (node (ref "Q1") (pin "1") (pinfunction "S_1") (pintype "passive"))
      (node (ref "Q1") (pin "2") (pinfunction "S_2") (pintype "passive"))
      (node (ref "Q1") (pin "3") (pinfunction "S_3") (pintype "passive"))
    )
    (net (code "51") (name "Net-(LED1-A)") (class "Default")
      (node (ref "LED1") (pin "2") (pinfunction "A_2") (pintype "passive"))
      (node (ref "R3") (pin "2") (pinfunction "2_2") (pintype "passive"))
    )
    (net (code "52") (name "Net-(Q1-G)") (class "Default")
      (node (ref "Q1") (pin "4") (pinfunction "G_4") (pintype "passive"))
      (node (ref "U2") (pin "1") (pinfunction "VBUSG_1") (pintype "passive"))
    )
    (net (code "53") (name "Net-(Q3-C)") (class "Default")
      (node (ref "Q3") (pin "3") (pinfunction "C_3") (pintype "passive"))
      (node (ref "R12") (pin "1") (pinfunction "1_1") (pintype "passive"))
      (node (ref "R14") (pin "2") (pinfunction "2_2") (pintype "passive"))
    )
    (net (code "54") (name "Net-(U1-BOOT0)") (class "Default")
      (node (ref "R2") (pin "1") (pinfunction "1_1") (pintype "passive"))
      (node (ref "U1") (pin "44") (pinfunction "BOOT0_44") (pintype "passive"))
    )
    (net (code "55") (name "Net-(U1-VDDA)") (class "Default")
      (node (ref "C1") (pin "2") (pinfunction "2_2") (pintype "passive"))
      (node (ref "R1") (pin "2") (pinfunction "2_2") (pintype "passive"))
      (node (ref "U1") (pin "9") (pinfunction "VDDA_9") (pintype "passive"))
    )
    (net (code "56") (name "Net-(U2-SEL)") (class "Default")
      (node (ref "R6") (pin "1") (pinfunction "1_1") (pintype "passive"))
      (node (ref "U2") (pin "11") (pinfunction "SEL_11") (pintype "passive"))
    )
    (net (code "57") (name "Net-(U11-OUTH)") (class "Default")
      (node (ref "R20") (pin "2") (pinfunction "2_2") (pintype "passive"))
      (node (ref "U11") (pin "2") (pinfunction "OUTH_2") (pintype "passive"))
    )
    (net (code "58") (name "Net-(U11-OUTL)") (class "Default")
      (node (ref "R21") (pin "2") (pinfunction "2_2") (pintype "passive"))
      (node (ref "U11") (pin "3") (pinfunction "OUTL_3") (pintype "passive"))
    )
    (net (code "59") (name "Net-(U13-BST)") (class "Default")
      (node (ref "C21") (pin "1") (pinfunction "1_1") (pintype "passive"))
      (node (ref "U13") (pin "1") (pinfunction "BST_1") (pintype "passive"))
    )
    (net (code "60") (name "Net-(U13-EN)") (class "Default")
      (node (ref "R22") (pin "1") (pinfunction "1_1") (pintype "passive"))
      (node (ref "U13") (pin "4") (pinfunction "EN_4") (pintype "passive"))
    )
    (net (code "61") (name "Net-(U13-FB)") (class "Default")
      (node (ref "C23") (pin "1") (pinfunction "1_1") (pintype "passive"))
      (node (ref "R23") (pin "1") (pinfunction "1_1") (pintype "passive"))
      (node (ref "R24") (pin "2") (pinfunction "2_2") (pintype "passive"))
      (node (ref "U13") (pin "3") (pinfunction "FB_3") (pintype "passive"))
    )
    (net (code "62") (name "VBUS") (class "Default")
      (node (ref "C6") (pin "2") (pinfunction "2_2") (pintype "passive"))
      (node (ref "Q1") (pin "5") (pinfunction "D_5") (pintype "passive"))
      (node (ref "Q1") (pin "6") (pinfunction "D_6") (pintype "passive"))
      (node (ref "Q1") (pin "7") (pinfunction "D_7") (pintype "passive"))
      (node (ref "Q1") (pin "8") (pinfunction "D_8") (pintype "passive"))
      (node (ref "R6") (pin "2") (pinfunction "2_2") (pintype "passive"))
      (node (ref "U2") (pin "2") (pinfunction "VIN_2") (pintype "passive"))
      (node (ref "USB1") (pin "A9") (pinfunction "VBUS_A9") (pintype "passive"))
      (node (ref "USB1") (pin "B9") (pinfunction "VBUS_B9") (pintype "passive"))
    )
    (net (code "63") (name "unconnected-(U2-NC-Pad3)") (class "Default")
      (node (ref "U2") (pin "3") (pinfunction "NC_3") (pintype "passive+no_connect"))
    )
    (net (code "64") (name "unconnected-(U2-NC-Pad4)") (class "Default")
      (node (ref "U2") (pin "4") (pinfunction "NC_4") (pintype "passive+no_connect"))
    )
    (net (code "65") (name "unconnected-(U2-NC-Pad9)") (class "Default")
      (node (ref "U2") (pin "9") (pinfunction "NC_9") (pintype "passive+no_connect"))
    )
    (net (code "66") (name "unconnected-(U2-NC-Pad10)") (class "Default")
      (node (ref "U2") (pin "10") (pinfunction "NC_10") (pintype "passive+no_connect"))
    )
    (net (code "67") (name "unconnected-(U2-NC-Pad14)") (class "Default")
      (node (ref "U2") (pin "14") (pinfunction "NC_14") (pintype "passive+no_connect"))
    )
    (net (code "68") (name "unconnected-(U2-NC-Pad15)") (class "Default")
      (node (ref "U2") (pin "15") (pinfunction "NC_15") (pintype "passive+no_connect"))
    )
    (net (code "69") (name "unconnected-(U2-TST1-Pad6)") (class "Default")
      (node (ref "U2") (pin "6") (pinfunction "TST1_6") (pintype "passive+no_connect"))
    )
    (net (code "70") (name "unconnected-(U2-TST2-Pad7)") (class "Default")
      (node (ref "U2") (pin "7") (pinfunction "TST2_7") (pintype "passive+no_connect"))
    )
    (net (code "71") (name "unconnected-(U2-TST3-Pad8)") (class "Default")
      (node (ref "U2") (pin "8") (pinfunction "TST3_8") (pintype "passive+no_connect"))
    )
    (net (code "72") (name "unconnected-(U2-VBUS-Pad16)") (class "Default")
      (node (ref "U2") (pin "16") (pinfunction "VBUS_16") (pintype "passive"))
    )
    (net (code "73") (name "unconnected-(X1-Pad16)") (class "Default")
      (node (ref "X1") (pin "16") (pinfunction "16_16") (pintype "passive+no_connect"))
    )
    (net (code "74") (name "unconnected-(X1-Pad17)") (class "Default")
      (node (ref "X1") (pin "17") (pinfunction "17_17") (pintype "passive+no_connect"))
    )
  )
)
